# GBA_DMG.net
KiCad netlist of a schematic drawn in Altium Designer
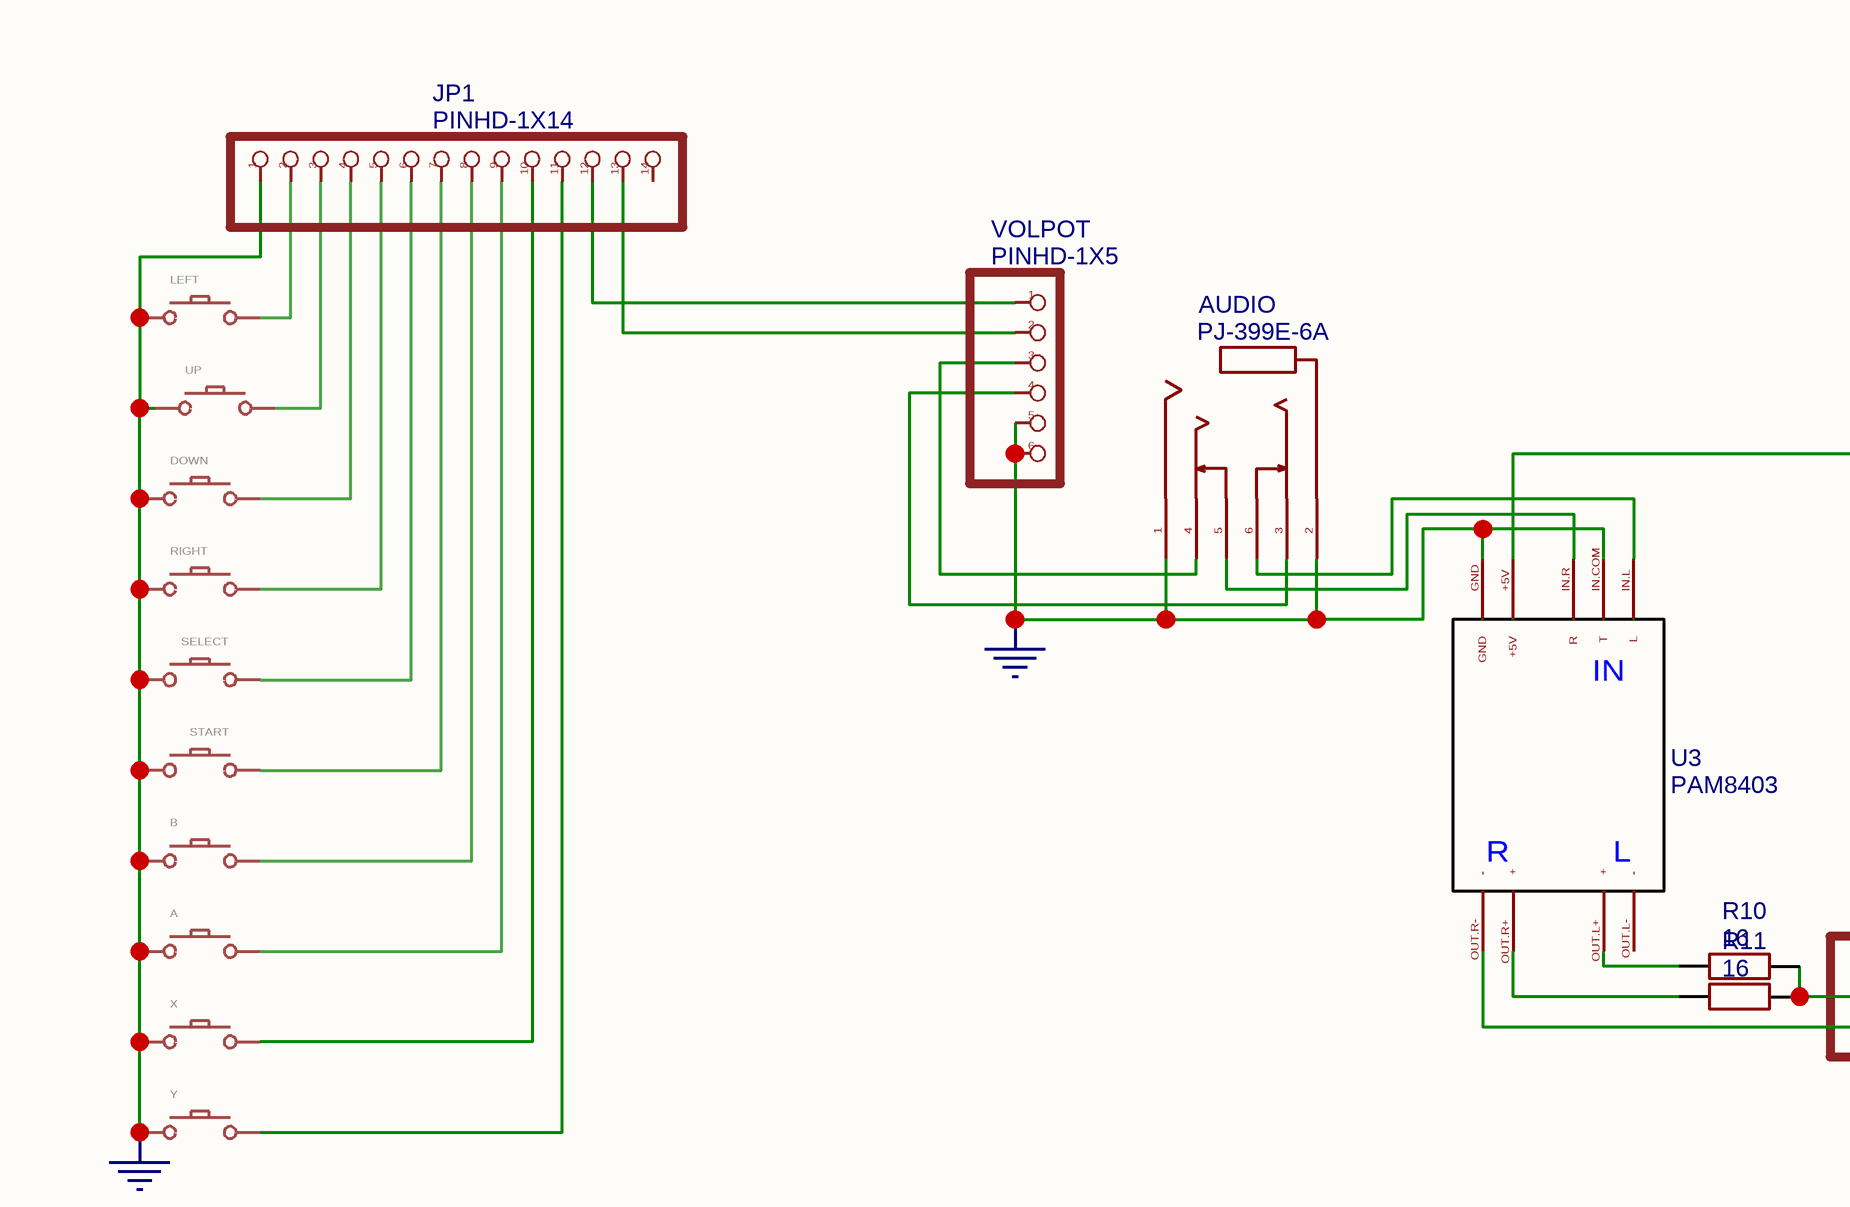
[diagram p0: GBA_DMG.schdoc, top left]
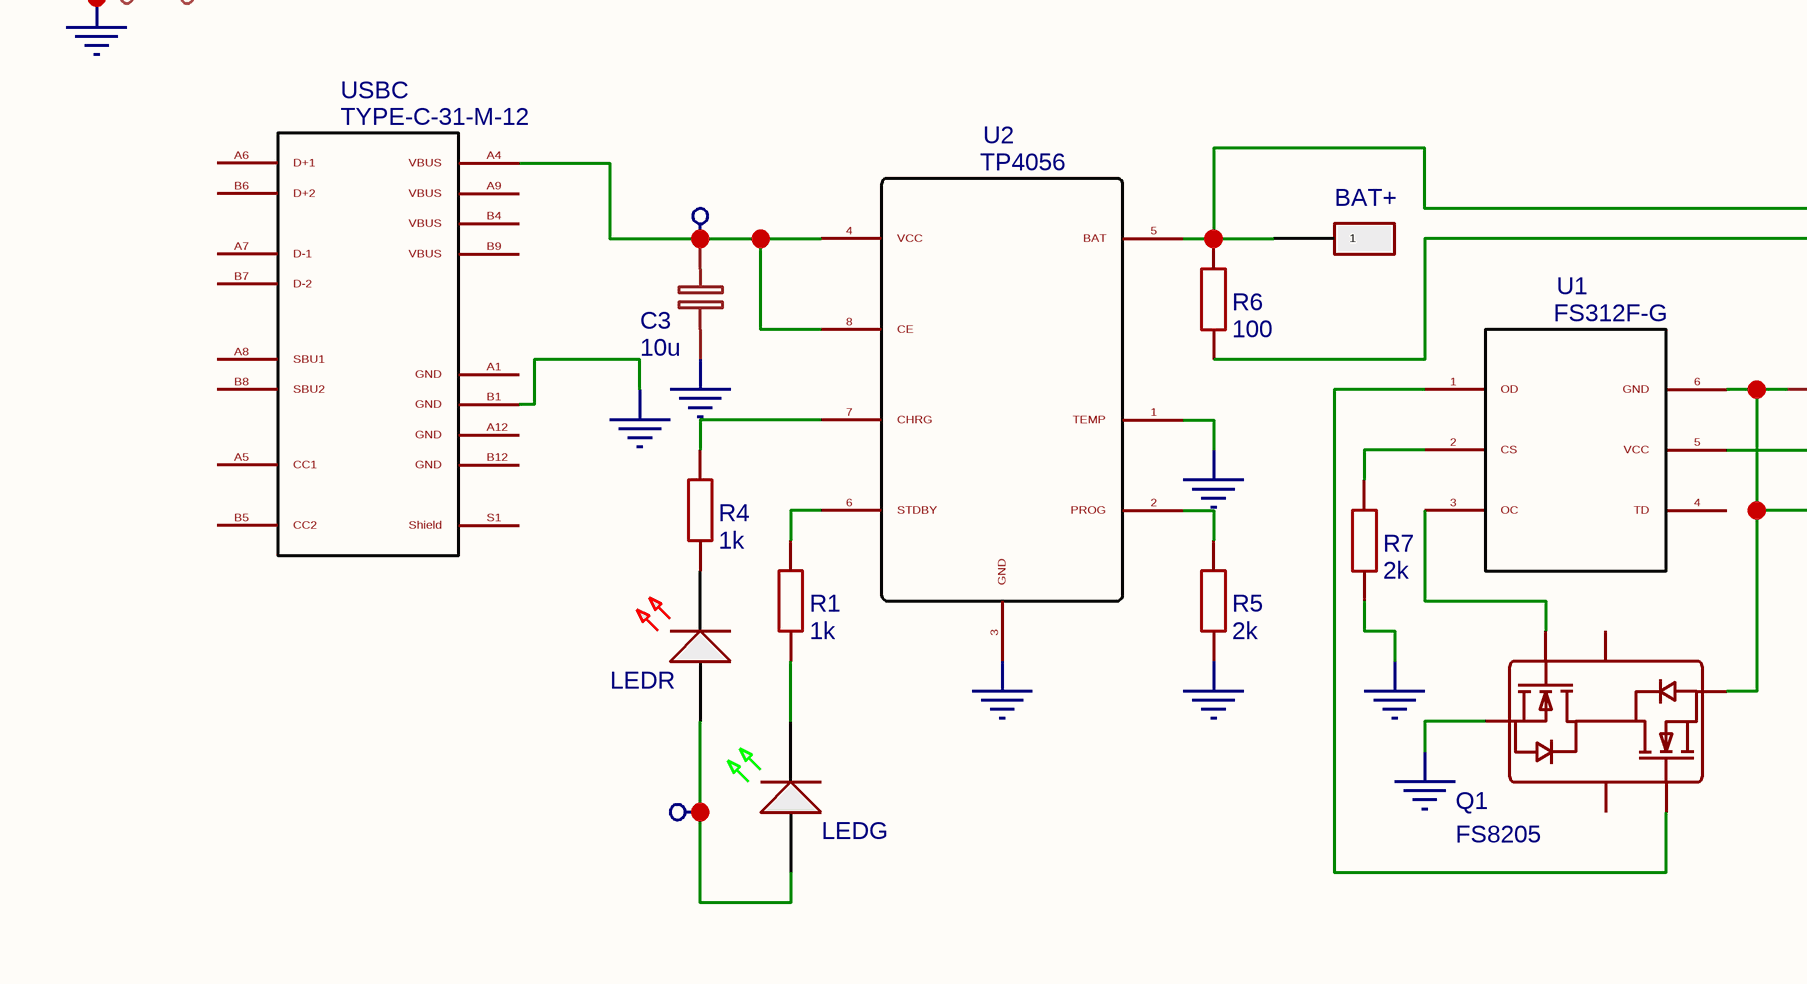
[diagram p1: GBA_DMG.schdoc, bottom left]
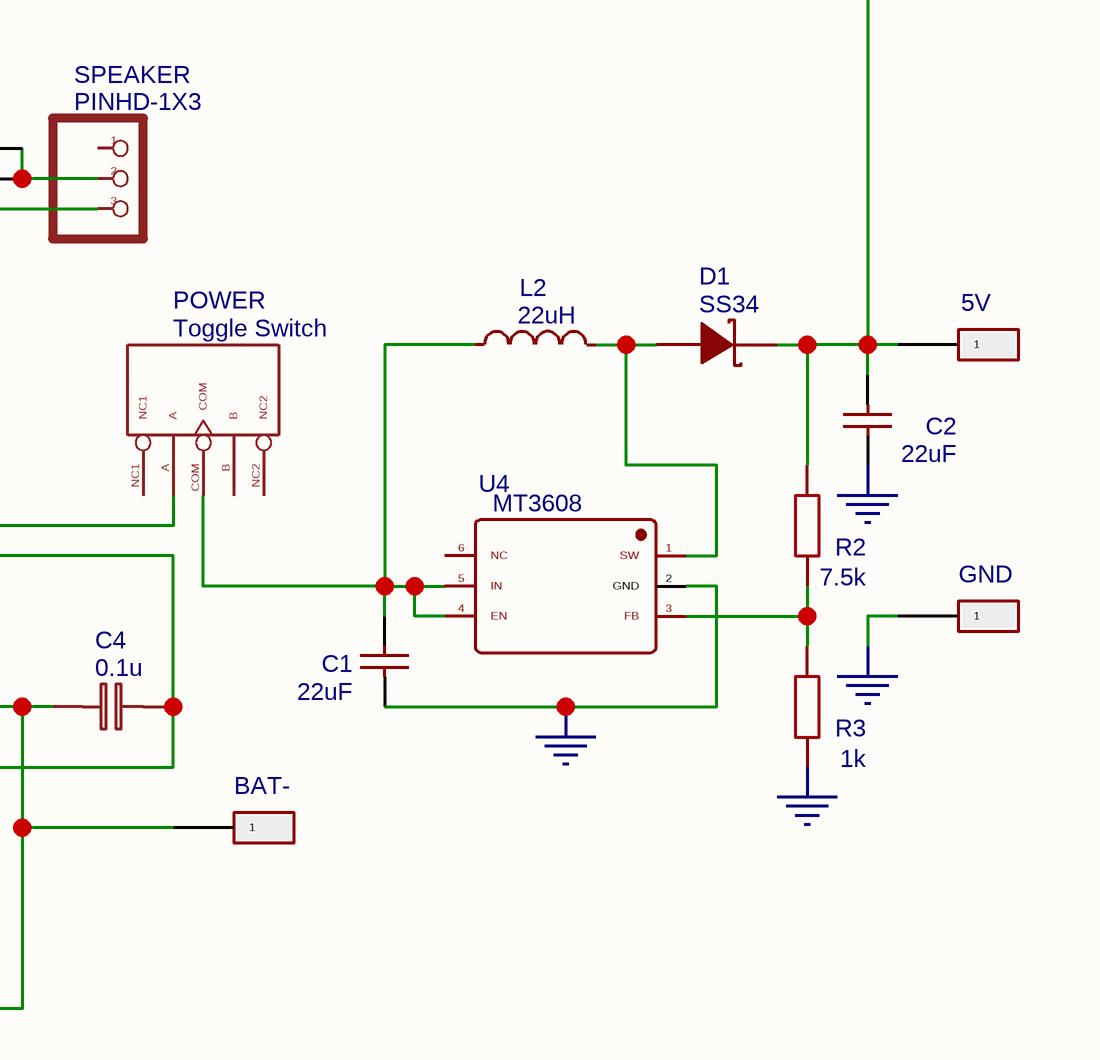
[diagram p2: GBA_DMG.schdoc, bottom right]

(export (version "E")
  (design (tool "Eeschema 10.0.6"))
  (components
    (comp (ref "5V")
      (value "5V")
      (fields
        (field (name "BOM_MANUFACTURER PART") "Header-Male-2.54_1x1")
        (field (name "BOM_SUPPLIER PART") "C81276")
      )
      (libsource (lib "altium-import") (part "root_2__"))
    )
    (comp (ref "A") (value "DMG-BTN") (libsource (lib "") (part "root_0___2")))
    (comp (ref "AUDIO")
      (value "PJ-399E-6A")
      (fields (field (name "BOM_SUPPLIER PART") "C128993") (field (name "CONTRIBUTOR") "LCSC"))
      (libsource (lib "altium-import") (part "root_3__"))
    )
    (comp (ref "B") (value "DMG-BTN") (libsource (lib "") (part "root_0___2")))
    (comp (ref "BAT+")
      (value "BAT+")
      (fields
        (field (name "BOM_MANUFACTURER PART") "Header-Male-2.54_1x1")
        (field (name "BOM_SUPPLIER PART") "C81276")
      )
      (libsource (lib "") (part "root_0___5"))
    )
    (comp (ref "BAT-")
      (value "BAT-")
      (fields
        (field (name "BOM_MANUFACTURER PART") "Header-Male-2.54_1x1")
        (field (name "BOM_SUPPLIER PART") "C81276")
      )
      (libsource (lib "") (part "root_0___5"))
    )
    (comp (ref "C1")
      (value "22uF")
      (fields
        (field (name "VOLTAGE") "25V")
        (field (name "TOLERANCE") "±10%")
        (field (name "BOM_MANUFACTURER PART") "1812X226K250NT")
      )
      (libsource (lib "") (part "root_1___4"))
    )
    (comp (ref "C2")
      (value "22uF")
      (fields
        (field (name "VOLTAGE") "25V")
        (field (name "TOLERANCE") "±10%")
        (field (name "BOM_MANUFACTURER PART") "1812X226K250NT")
      )
      (libsource (lib "") (part "root_3___1"))
    )
    (comp (ref "C3")
      (value "10u")
      (fields (field (name "BOM_MANUFACTURER PART") "?"))
      (libsource (lib "") (part "root_0___12"))
    )
    (comp (ref "C4")
      (value "0.1u")
      (fields (field (name "BOM_MANUFACTURER PART") "?"))
      (libsource (lib "") (part "root_1___1"))
    )
    (comp (ref "D1")
      (value "SS34")
      (fields (field (name "BOM_SUPPLIER PART") "C8678"))
      (libsource (lib "") (part "root_0___14"))
    )
    (comp (ref "DOWN") (value "DMG-BTN") (libsource (lib "") (part "root_0___2")))
    (comp (ref "GND")
      (value "GND")
      (fields
        (field (name "BOM_MANUFACTURER PART") "Header-Male-2.54_1x1")
        (field (name "BOM_SUPPLIER PART") "C81276")
      )
      (libsource (lib "") (part "root_0___5"))
    )
    (comp (ref "JP1")
      (value "PINHD-1X14")
      (fields (field (name "BOM_MANUFACTURER PART") "?") (field (name "CONTRIBUTOR") "Adafruit"))
      (libsource (lib "") (part "root_1___2"))
    )
    (comp (ref "L2")
      (value "22uH")
      (fields
        (field (name "BOM_MANUFACTURER PART") "SMRH74-220MT")
        (field (name "BOM_SUPPLIER PART") "C27442")
      )
      (libsource (lib "") (part "root_0___3"))
    )
    (comp (ref "LEDG")
      (value "19-217/GHC-YR1S2/3T")
      (fields (field (name "BOM_SUPPLIER PART") "C72043"))
      (libsource (lib "") (part "root_1___5"))
    )
    (comp (ref "LEDR")
      (value "Red(0603)")
      (fields (field (name "BOM_MANUFACTURER PART") "KT-0603R") (field (name "BOM_SUPPLIER PART") "C2286"))
      (libsource (lib "") (part "root_1___5"))
    )
    (comp (ref "LEFT") (value "DMG-BTN") (libsource (lib "") (part "root_0___6")))
    (comp (ref "POWER")
      (value "Toggle Switch")
      (description "DIP Toggle Switch ON-ON; 0.3A- AC 500V")
      (fields (field (name "BOM_MANUFACTURER PART") "3P-2.0-90D-REINFORCE;"))
      (libsource (lib "") (part "root_1___3"))
    )
    (comp (ref "Q1")
      (value "FS8205")
      (fields (field (name "BOM_SUPPLIER PART") "C32254"))
      (libsource (lib "") (part "root_0___7"))
    )
    (comp (ref "R1")
      (value "1k")
      (fields (field (name "BOM_MANUFACTURER PART") "?"))
      (libsource (lib "altium-import") (part "root_1__"))
    )
    (comp (ref "R2")
      (value "7.5k")
      (fields (field (name "BOM_MANUFACTURER PART") "?"))
      (libsource (lib "altium-import") (part "root_1__"))
    )
    (comp (ref "R3")
      (value "1k")
      (fields (field (name "BOM_MANUFACTURER PART") "?"))
      (libsource (lib "altium-import") (part "root_1__"))
    )
    (comp (ref "R4")
      (value "1k")
      (fields (field (name "BOM_MANUFACTURER PART") "?"))
      (libsource (lib "altium-import") (part "root_1__"))
    )
    (comp (ref "R5")
      (value "2k")
      (fields (field (name "BOM_MANUFACTURER PART") "?"))
      (libsource (lib "altium-import") (part "root_1__"))
    )
    (comp (ref "R6")
      (value "100")
      (fields (field (name "BOM_MANUFACTURER PART") "?"))
      (libsource (lib "altium-import") (part "root_1__"))
    )
    (comp (ref "R7")
      (value "2k")
      (fields (field (name "BOM_MANUFACTURER PART") "?"))
      (libsource (lib "altium-import") (part "root_1__"))
    )
    (comp (ref "R10")
      (value "16")
      (fields
        (field (name "BOM_MANUFACTURER PART") "0805W8J0202T5E")
        (field (name "BOM_SUPPLIER PART") "C1359")
        (field (name "CONTRIBUTOR") "LCSC")
      )
      (libsource (lib "") (part "root_0___1"))
    )
    (comp (ref "R11")
      (value "16")
      (fields
        (field (name "BOM_MANUFACTURER PART") "0805W8J0202T5E")
        (field (name "BOM_SUPPLIER PART") "C1359")
        (field (name "CONTRIBUTOR") "LCSC")
      )
      (libsource (lib "") (part "root_0___1"))
    )
    (comp (ref "RIGHT") (value "DMG-BTN") (libsource (lib "") (part "root_0___2")))
    (comp (ref "SELECT") (value "DMG-BTN") (libsource (lib "") (part "root_0___4")))
    (comp (ref "SPEAKER")
      (value "PINHD-1X3")
      (fields (field (name "BOM_MANUFACTURER PART") "?") (field (name "CONTRIBUTOR") "Adafruit"))
      (libsource (lib "") (part "root_0___11"))
    )
    (comp (ref "START") (value "DMG-BTN") (libsource (lib "") (part "root_0___4")))
    (comp (ref "U1")
      (value "FS312F-G")
      (fields (field (name "BOM_MANUFACTURER PART") "DW01+G") (field (name "BOM_SUPPLIER PART") "C14213"))
      (libsource (lib "") (part "root_0___10"))
    )
    (comp (ref "U2")
      (value "TP4056")
      (fields (field (name "BOM_SUPPLIER PART") "C16581") (field (name "CONTRIBUTOR") "Guest"))
      (libsource (lib "") (part "root_0___13"))
    )
    (comp (ref "U3")
      (value "PAM8403")
      (fields (field (name "CONTRIBUTOR") "kiranmalshikhare55"))
      (libsource (lib "") (part "root_2___1"))
    )
    (comp (ref "U4")
      (value "MT3608")
      (fields (field (name "BOM_SUPPLIER PART") "C84817"))
      (libsource (lib "") (part "root_0___8"))
    )
    (comp (ref "UP") (value "DMG-BTN") (libsource (lib "") (part "root_0___2")))
    (comp (ref "USBC")
      (value "TYPE-C-31-M-12")
      (fields (field (name "BOM_MANUFACTURER PART") "?") (field (name "CONTRIBUTOR") "marcelroder3"))
      (libsource (lib "") (part "root_0___9"))
    )
    (comp (ref "VOLPOT")
      (value "PINHD-1X5")
      (fields (field (name "BOM_MANUFACTURER PART") "?") (field (name "CONTRIBUTOR") "Adafruit"))
      (libsource (lib "altium-import") (part "root_0__"))
    )
    (comp (ref "X") (value "DMG-BTN") (libsource (lib "") (part "root_0___2")))
    (comp (ref "Y") (value "DMG-BTN") (libsource (lib "") (part "root_0___2")))
  )
  (nets
    (net (code "1") (name "GND") (class "Default")
      (node (ref "A") (pin "P$1") (pinfunction "P$1_P$1") (pintype "passive"))
      (node (ref "AUDIO") (pin "1") (pinfunction "1_1") (pintype "passive"))
      (node (ref "AUDIO") (pin "2") (pinfunction "2_2") (pintype "passive"))
      (node (ref "B") (pin "P$1") (pinfunction "P$1_P$1") (pintype "passive"))
      (node (ref "C1") (pin "1") (pinfunction "1_1") (pintype "passive"))
      (node (ref "C2") (pin "2") (pinfunction "2_2") (pintype "passive"))
      (node (ref "C3") (pin "2") (pinfunction "2_2") (pintype "passive"))
      (node (ref "DOWN") (pin "P$1") (pinfunction "P$1_P$1") (pintype "passive"))
      (node (ref "GND") (pin "1") (pinfunction "1_1") (pintype "passive"))
      (node (ref "JP1") (pin "1") (pinfunction "1_1") (pintype "passive"))
      (node (ref "LEFT") (pin "P$1") (pinfunction "P$1_P$1") (pintype "passive"))
      (node (ref "Q1") (pin "1") (pinfunction "S1_1") (pintype "passive"))
      (node (ref "R3") (pin "1") (pinfunction "1_1") (pintype "passive"))
      (node (ref "R5") (pin "1") (pinfunction "1_1") (pintype "passive"))
      (node (ref "R7") (pin "1") (pinfunction "1_1") (pintype "passive"))
      (node (ref "RIGHT") (pin "P$1") (pinfunction "P$1_P$1") (pintype "passive"))
      (node (ref "SELECT") (pin "P$2") (pinfunction "P$2_P$2") (pintype "passive"))
      (node (ref "START") (pin "P$2") (pinfunction "P$2_P$2") (pintype "passive"))
      (node (ref "U2") (pin "1") (pinfunction "TEMP_1") (pintype "passive"))
      (node (ref "U2") (pin "3") (pinfunction "GND_3") (pintype "passive"))
      (node (ref "U3") (pin "GND") (pinfunction "GND_GND") (pintype "passive"))
      (node (ref "U3") (pin "IN.COM") (pinfunction "T_IN.COM") (pintype "passive"))
      (node (ref "U4") (pin "2") (pinfunction "GND_2") (pintype "passive"))
      (node (ref "UP") (pin "P$1") (pinfunction "P$1_P$1") (pintype "passive"))
      (node (ref "USBC") (pin "B1") (pinfunction "GND_B1") (pintype "passive"))
      (node (ref "VOLPOT") (pin "5") (pinfunction "5_5") (pintype "passive"))
      (node (ref "VOLPOT") (pin "6") (pinfunction "6_6") (pintype "passive"))
      (node (ref "X") (pin "P$1") (pinfunction "P$1_P$1") (pintype "passive"))
      (node (ref "Y") (pin "P$1") (pinfunction "P$1_P$1") (pintype "passive"))
    )
    (net (code "2") (name "Net-(A-PadP$2)") (class "Default")
      (node (ref "A") (pin "P$2") (pinfunction "P$2_P$2") (pintype "passive"))
      (node (ref "JP1") (pin "9") (pinfunction "9_9") (pintype "passive"))
    )
    (net (code "3") (name "Net-(AUDIO-Pad3)") (class "Default")
      (node (ref "AUDIO") (pin "3") (pinfunction "3_3") (pintype "passive"))
      (node (ref "VOLPOT") (pin "4") (pinfunction "4_4") (pintype "passive"))
    )
    (net (code "4") (name "Net-(AUDIO-Pad4)") (class "Default")
      (node (ref "AUDIO") (pin "4") (pinfunction "4_4") (pintype "passive"))
      (node (ref "VOLPOT") (pin "3") (pinfunction "3_3") (pintype "passive"))
    )
    (net (code "5") (name "Net-(B-PadP$2)") (class "Default")
      (node (ref "B") (pin "P$2") (pinfunction "P$2_P$2") (pintype "passive"))
      (node (ref "JP1") (pin "8") (pinfunction "8_8") (pintype "passive"))
    )
    (net (code "6") (name "Net-(D1-A)") (class "Default")
      (node (ref "D1") (pin "1") (pinfunction "A_1") (pintype "passive"))
      (node (ref "L2") (pin "2") (pinfunction "2_2") (pintype "passive"))
      (node (ref "U4") (pin "1") (pinfunction "SW_1") (pintype "passive"))
    )
    (net (code "7") (name "Net-(D1-K)") (class "Default")
      (node (ref "5V") (pin "1") (pinfunction "1_1") (pintype "passive"))
      (node (ref "C2") (pin "1") (pinfunction "1_1") (pintype "passive"))
      (node (ref "D1") (pin "2") (pinfunction "K_2") (pintype "passive"))
      (node (ref "R2") (pin "2") (pinfunction "2_2") (pintype "passive"))
      (node (ref "U3") (pin "+5V") (pinfunction "+5V_+5V") (pintype "passive"))
    )
    (net (code "8") (name "Net-(DOWN-PadP$2)") (class "Default")
      (node (ref "DOWN") (pin "P$2") (pinfunction "P$2_P$2") (pintype "passive"))
      (node (ref "JP1") (pin "4") (pinfunction "4_4") (pintype "passive"))
    )
    (net (code "9") (name "Net-(JP1-Pad2)") (class "Default")
      (node (ref "JP1") (pin "2") (pinfunction "2_2") (pintype "passive"))
      (node (ref "LEFT") (pin "P$2") (pinfunction "P$2_P$2") (pintype "passive"))
    )
    (net (code "10") (name "Net-(JP1-Pad3)") (class "Default")
      (node (ref "JP1") (pin "3") (pinfunction "3_3") (pintype "passive"))
      (node (ref "UP") (pin "P$2") (pinfunction "P$2_P$2") (pintype "passive"))
    )
    (net (code "11") (name "Net-(JP1-Pad5)") (class "Default")
      (node (ref "JP1") (pin "5") (pinfunction "5_5") (pintype "passive"))
      (node (ref "RIGHT") (pin "P$2") (pinfunction "P$2_P$2") (pintype "passive"))
    )
    (net (code "12") (name "Net-(JP1-Pad6)") (class "Default")
      (node (ref "JP1") (pin "6") (pinfunction "6_6") (pintype "passive"))
      (node (ref "SELECT") (pin "P$1") (pinfunction "P$1_P$1") (pintype "passive"))
    )
    (net (code "13") (name "Net-(JP1-Pad7)") (class "Default")
      (node (ref "JP1") (pin "7") (pinfunction "7_7") (pintype "passive"))
      (node (ref "START") (pin "P$1") (pinfunction "P$1_P$1") (pintype "passive"))
    )
    (net (code "14") (name "Net-(JP1-Pad10)") (class "Default")
      (node (ref "JP1") (pin "10") (pinfunction "10_10") (pintype "passive"))
      (node (ref "X") (pin "P$2") (pinfunction "P$2_P$2") (pintype "passive"))
    )
    (net (code "15") (name "Net-(JP1-Pad11)") (class "Default")
      (node (ref "JP1") (pin "11") (pinfunction "11_11") (pintype "passive"))
      (node (ref "Y") (pin "P$2") (pinfunction "P$2_P$2") (pintype "passive"))
    )
    (net (code "16") (name "Net-(JP1-Pad12)") (class "Default")
      (node (ref "JP1") (pin "12") (pinfunction "12_12") (pintype "passive"))
      (node (ref "VOLPOT") (pin "1") (pinfunction "1_1") (pintype "passive"))
    )
    (net (code "17") (name "Net-(JP1-Pad13)") (class "Default")
      (node (ref "JP1") (pin "13") (pinfunction "13_13") (pintype "passive"))
      (node (ref "VOLPOT") (pin "2") (pinfunction "2_2") (pintype "passive"))
    )
    (net (code "18") (name "Net-(LEDG-C)") (class "Default")
      (node (ref "LEDG") (pin "2") (pinfunction "C_2") (pintype "passive"))
      (node (ref "R1") (pin "1") (pinfunction "1_1") (pintype "passive"))
    )
    (net (code "19") (name "Net-(LEDR-C)") (class "Default")
      (node (ref "LEDR") (pin "2") (pinfunction "C_2") (pintype "passive"))
      (node (ref "R4") (pin "1") (pinfunction "1_1") (pintype "passive"))
    )
    (net (code "20") (name "Net-(Q1-G1)") (class "Default")
      (node (ref "Q1") (pin "6") (pinfunction "G1_6") (pintype "passive"))
      (node (ref "U1") (pin "3") (pinfunction "OC_3") (pintype "passive"))
    )
    (net (code "21") (name "Net-(Q1-G2)") (class "Default")
      (node (ref "Q1") (pin "4") (pinfunction "G2_4") (pintype "passive"))
      (node (ref "U1") (pin "1") (pinfunction "OD_1") (pintype "passive"))
    )
    (net (code "22") (name "Net-(Q1-S2)") (class "Default")
      (node (ref "BAT-") (pin "1") (pinfunction "1_1") (pintype "passive"))
      (node (ref "C4") (pin "1") (pinfunction "1_1") (pintype "passive"))
      (node (ref "Q1") (pin "3") (pinfunction "S2_3") (pintype "passive"))
      (node (ref "U1") (pin "6") (pinfunction "GND_6") (pintype "passive"))
    )
    (net (code "23") (name "Net-(R10-Pad1)") (class "Default")
      (node (ref "R10") (pin "1") (pinfunction "1_1") (pintype "passive"))
      (node (ref "U3") (pin "OUT.L+") (pinfunction "+_OUT.L+") (pintype "passive"))
    )
    (net (code "24") (name "Net-(R10-Pad2)") (class "Default")
      (node (ref "R10") (pin "2") (pinfunction "2_2") (pintype "passive"))
      (node (ref "R11") (pin "2") (pinfunction "2_2") (pintype "passive"))
      (node (ref "SPEAKER") (pin "2") (pinfunction "2_2") (pintype "passive"))
    )
    (net (code "25") (name "Net-(R11-Pad1)") (class "Default")
      (node (ref "R11") (pin "1") (pinfunction "1_1") (pintype "passive"))
      (node (ref "U3") (pin "OUT.R+") (pinfunction "+_OUT.R+") (pintype "passive"))
    )
    (net (code "26") (name "Net-(SPEAKER-Pad3)") (class "Default")
      (node (ref "SPEAKER") (pin "3") (pinfunction "3_3") (pintype "passive"))
      (node (ref "U3") (pin "OUT.R-") (pinfunction "-_OUT.R-") (pintype "passive"))
    )
    (net (code "27") (name "Net-(U1-CS)") (class "Default")
      (node (ref "R7") (pin "2") (pinfunction "2_2") (pintype "passive"))
      (node (ref "U1") (pin "2") (pinfunction "CS_2") (pintype "passive"))
    )
    (net (code "28") (name "Net-(U1-VCC)") (class "Default")
      (node (ref "C4") (pin "2") (pinfunction "2_2") (pintype "passive"))
      (node (ref "R6") (pin "1") (pinfunction "1_1") (pintype "passive"))
      (node (ref "U1") (pin "5") (pinfunction "VCC_5") (pintype "passive"))
    )
    (net (code "29") (name "Net-(U2-BAT)") (class "Default")
      (node (ref "BAT+") (pin "1") (pinfunction "1_1") (pintype "passive"))
      (node (ref "POWER") (pin "A") (pinfunction "A_A") (pintype "passive"))
      (node (ref "R6") (pin "2") (pinfunction "2_2") (pintype "passive"))
      (node (ref "U2") (pin "5") (pinfunction "BAT_5") (pintype "passive"))
    )
    (net (code "30") (name "Net-(U2-CHRG)") (class "Default")
      (node (ref "R4") (pin "2") (pinfunction "2_2") (pintype "passive"))
      (node (ref "U2") (pin "7") (pinfunction "CHRG_7") (pintype "passive"))
    )
    (net (code "31") (name "Net-(U2-PROG)") (class "Default")
      (node (ref "R5") (pin "2") (pinfunction "2_2") (pintype "passive"))
      (node (ref "U2") (pin "2") (pinfunction "PROG_2") (pintype "passive"))
    )
    (net (code "32") (name "Net-(U2-STDBY)") (class "Default")
      (node (ref "R1") (pin "2") (pinfunction "2_2") (pintype "passive"))
      (node (ref "U2") (pin "6") (pinfunction "STDBY_6") (pintype "passive"))
    )
    (net (code "33") (name "Net-(U3-L)") (class "Default")
      (node (ref "AUDIO") (pin "6") (pinfunction "6_6") (pintype "passive"))
      (node (ref "U3") (pin "IN.L") (pinfunction "L_IN.L") (pintype "passive"))
    )
    (net (code "34") (name "Net-(U3-R)") (class "Default")
      (node (ref "AUDIO") (pin "5") (pinfunction "5_5") (pintype "passive"))
      (node (ref "U3") (pin "IN.R") (pinfunction "R_IN.R") (pintype "passive"))
    )
    (net (code "35") (name "Net-(U4-EN)") (class "Default")
      (node (ref "C1") (pin "2") (pinfunction "2_2") (pintype "passive"))
      (node (ref "L2") (pin "1") (pinfunction "1_1") (pintype "passive"))
      (node (ref "POWER") (pin "COM") (pinfunction "COM_COM") (pintype "passive"))
      (node (ref "U4") (pin "4") (pinfunction "EN_4") (pintype "passive"))
      (node (ref "U4") (pin "5") (pinfunction "IN_5") (pintype "passive"))
    )
    (net (code "36") (name "Net-(U4-FB)") (class "Default")
      (node (ref "R2") (pin "1") (pinfunction "1_1") (pintype "passive"))
      (node (ref "R3") (pin "2") (pinfunction "2_2") (pintype "passive"))
      (node (ref "U4") (pin "3") (pinfunction "FB_3") (pintype "passive"))
    )
    (net (code "37") (name "VBUS") (class "Default")
      (node (ref "C3") (pin "1") (pinfunction "1_1") (pintype "passive"))
      (node (ref "LEDG") (pin "1") (pinfunction "A_1") (pintype "passive"))
      (node (ref "LEDR") (pin "1") (pinfunction "A_1") (pintype "passive"))
      (node (ref "U2") (pin "4") (pinfunction "VCC_4") (pintype "passive"))
      (node (ref "U2") (pin "8") (pinfunction "CE_8") (pintype "passive"))
      (node (ref "USBC") (pin "A4") (pinfunction "VBUS_A4") (pintype "passive"))
    )
    (net (code "38") (name "unconnected-(JP1-Pad14)") (class "Default")
      (node (ref "JP1") (pin "14") (pinfunction "14_14") (pintype "passive"))
    )
    (net (code "39") (name "unconnected-(POWER-PadB)") (class "Default")
      (node (ref "POWER") (pin "B") (pinfunction "B_B") (pintype "passive"))
    )
    (net (code "40") (name "unconnected-(POWER-PadNC1)") (class "Default")
      (node (ref "POWER") (pin "NC1") (pinfunction "NC1_NC1") (pintype "passive"))
    )
    (net (code "41") (name "unconnected-(POWER-PadNC2)") (class "Default")
      (node (ref "POWER") (pin "NC2") (pinfunction "NC2_NC2") (pintype "passive"))
    )
    (net (code "42") (name "unconnected-(Q1-D12-Pad2)") (class "Default")
      (node (ref "Q1") (pin "2") (pinfunction "D12_2") (pintype "passive"))
    )
    (net (code "43") (name "unconnected-(Q1-D12-Pad5)") (class "Default")
      (node (ref "Q1") (pin "5") (pinfunction "D12_5") (pintype "passive"))
    )
    (net (code "44") (name "unconnected-(SPEAKER-Pad1)") (class "Default")
      (node (ref "SPEAKER") (pin "1") (pinfunction "1_1") (pintype "passive"))
    )
    (net (code "45") (name "unconnected-(U1-TD-Pad4)") (class "Default")
      (node (ref "U1") (pin "4") (pinfunction "TD_4") (pintype "passive"))
    )
    (net (code "46") (name "unconnected-(U3---PadOUT.L-)") (class "Default")
      (node (ref "U3") (pin "OUT.L-") (pinfunction "-_OUT.L-") (pintype "passive"))
    )
    (net (code "47") (name "unconnected-(U4-NC-Pad6)") (class "Default")
      (node (ref "U4") (pin "6") (pinfunction "NC_6") (pintype "passive"))
    )
    (net (code "48") (name "unconnected-(USBC-CC1-PadA5)") (class "Default")
      (node (ref "USBC") (pin "A5") (pinfunction "CC1_A5") (pintype "passive"))
    )
    (net (code "49") (name "unconnected-(USBC-CC2-PadB5)") (class "Default")
      (node (ref "USBC") (pin "B5") (pinfunction "CC2_B5") (pintype "passive"))
    )
    (net (code "50") (name "unconnected-(USBC-D+1-PadA6)") (class "Default")
      (node (ref "USBC") (pin "A6") (pinfunction "D+1_A6") (pintype "passive"))
    )
    (net (code "51") (name "unconnected-(USBC-D+2-PadB6)") (class "Default")
      (node (ref "USBC") (pin "B6") (pinfunction "D+2_B6") (pintype "passive"))
    )
    (net (code "52") (name "unconnected-(USBC-D-1-PadA7)") (class "Default")
      (node (ref "USBC") (pin "A7") (pinfunction "D-1_A7") (pintype "passive"))
    )
    (net (code "53") (name "unconnected-(USBC-D-2-PadB7)") (class "Default")
      (node (ref "USBC") (pin "B7") (pinfunction "D-2_B7") (pintype "passive"))
    )
    (net (code "54") (name "unconnected-(USBC-GND-PadA1)") (class "Default")
      (node (ref "USBC") (pin "A1") (pinfunction "GND_A1") (pintype "passive"))
    )
    (net (code "55") (name "unconnected-(USBC-GND-PadA12)") (class "Default")
      (node (ref "USBC") (pin "A12") (pinfunction "GND_A12") (pintype "passive"))
    )
    (net (code "56") (name "unconnected-(USBC-GND-PadB12)") (class "Default")
      (node (ref "USBC") (pin "B12") (pinfunction "GND_B12") (pintype "passive"))
    )
    (net (code "57") (name "unconnected-(USBC-SBU1-PadA8)") (class "Default")
      (node (ref "USBC") (pin "A8") (pinfunction "SBU1_A8") (pintype "passive"))
    )
    (net (code "58") (name "unconnected-(USBC-SBU2-PadB8)") (class "Default")
      (node (ref "USBC") (pin "B8") (pinfunction "SBU2_B8") (pintype "passive"))
    )
    (net (code "59") (name "unconnected-(USBC-Shield-PadS1)") (class "Default")
      (node (ref "USBC") (pin "S1") (pinfunction "Shield_S1") (pintype "passive"))
    )
    (net (code "60") (name "unconnected-(USBC-VBUS-PadA9)") (class "Default")
      (node (ref "USBC") (pin "A9") (pinfunction "VBUS_A9") (pintype "passive"))
    )
    (net (code "61") (name "unconnected-(USBC-VBUS-PadB4)") (class "Default")
      (node (ref "USBC") (pin "B4") (pinfunction "VBUS_B4") (pintype "passive"))
    )
    (net (code "62") (name "unconnected-(USBC-VBUS-PadB9)") (class "Default")
      (node (ref "USBC") (pin "B9") (pinfunction "VBUS_B9") (pintype "passive"))
    )
  )
)
